# Microcontroller.net
KiCad netlist of a schematic drawn in Altium Designer
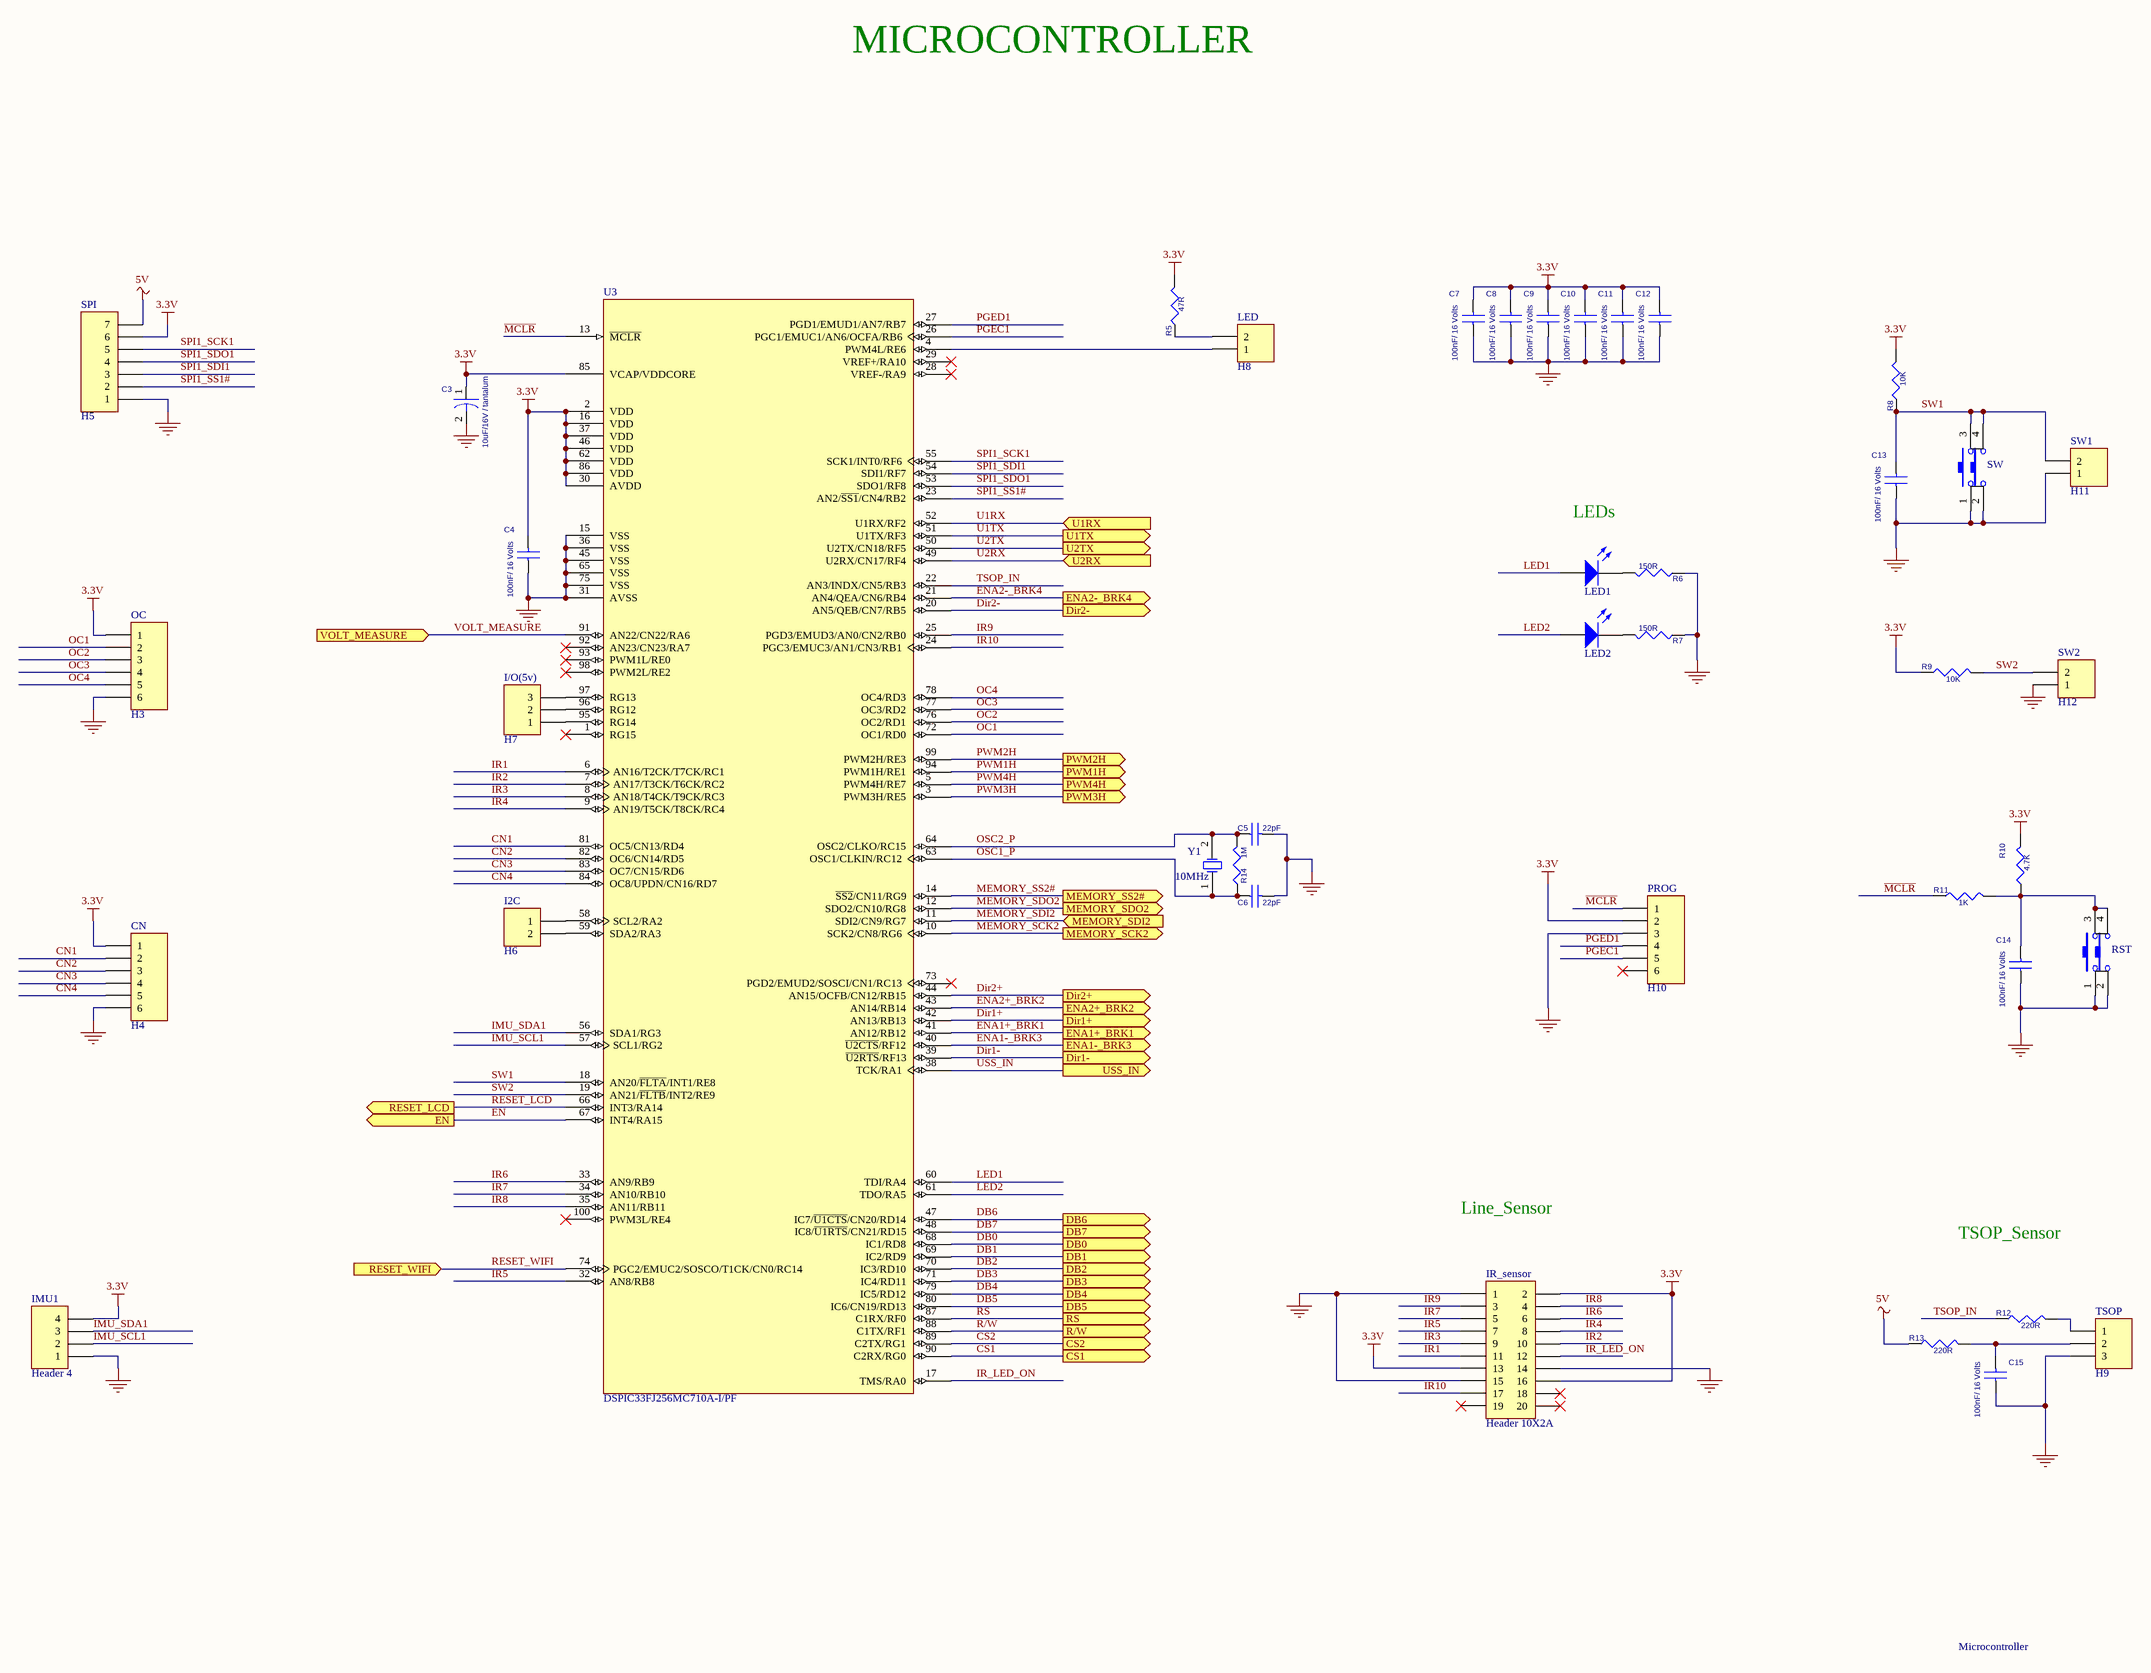
[diagram p0: Microcontroller.SchDoc]

(export (version "E")
  (design (tool "Eeschema 10.0.6"))
  (components
    (comp (ref "C3")
      (value "10uF/16V / tantalum")
      (footprint "CAP_TANTALUM")
      (libsource (lib "combined_cart_schematic_lib") (part "C_0"))
    )
    (comp (ref "C4")
      (value "100nF/ 16 Volts")
      (footprint "CAP_CERAMIC")
      (libsource (lib "combined_cart_schematic_lib") (part "CAP NP"))
    )
    (comp (ref "C5")
      (value "22pF")
      (footprint "CAP_CERAMIC")
      (libsource (lib "combined_cart_schematic_lib") (part "CAP NP"))
    )
    (comp (ref "C6")
      (value "22pF")
      (footprint "CAP_CERAMIC")
      (libsource (lib "combined_cart_schematic_lib") (part "CAP NP"))
    )
    (comp (ref "C7")
      (value "100nF/ 16 Volts")
      (footprint "CAP_CERAMIC")
      (libsource (lib "combined_cart_schematic_lib") (part "CAP NP"))
    )
    (comp (ref "C8")
      (value "100nF/ 16 Volts")
      (footprint "CAP_CERAMIC")
      (libsource (lib "combined_cart_schematic_lib") (part "CAP NP"))
    )
    (comp (ref "C9")
      (value "100nF/ 16 Volts")
      (footprint "CAP_CERAMIC")
      (libsource (lib "combined_cart_schematic_lib") (part "CAP NP"))
    )
    (comp (ref "C10")
      (value "100nF/ 16 Volts")
      (footprint "CAP_CERAMIC")
      (libsource (lib "combined_cart_schematic_lib") (part "CAP NP"))
    )
    (comp (ref "C11")
      (value "100nF/ 16 Volts")
      (footprint "CAP_CERAMIC")
      (libsource (lib "combined_cart_schematic_lib") (part "CAP NP"))
    )
    (comp (ref "C12")
      (value "100nF/ 16 Volts")
      (footprint "CAP_CERAMIC")
      (libsource (lib "combined_cart_schematic_lib") (part "CAP NP"))
    )
    (comp (ref "C13")
      (value "100nF/ 16 Volts")
      (footprint "CAP_CERAMIC")
      (libsource (lib "combined_cart_schematic_lib") (part "CAP NP"))
    )
    (comp (ref "C14")
      (value "100nF/ 16 Volts")
      (footprint "CAP_CERAMIC")
      (libsource (lib "combined_cart_schematic_lib") (part "CAP NP"))
    )
    (comp (ref "C15")
      (value "100nF/ 16 Volts")
      (footprint "CAP_CERAMIC")
      (libsource (lib "combined_cart_schematic_lib") (part "CAP NP"))
    )
    (comp (ref "CN")
      (value "H4")
      (footprint "1x6_single")
      (description "Header, 6-Pin")
      (fields (field (name "PUBLISHER") "Altium Limited"))
      (libsource (lib "combined_cart_schematic_lib") (part "Header 6"))
    )
    (comp (ref "I/O(5v)")
      (value "H7")
      (footprint "1x3_single - duplicate")
      (description "Header, 3-Pin")
      (fields (field (name "PUBLISHER") "Altium Limited"))
      (libsource (lib "combined_cart_schematic_lib") (part "Header 3"))
    )
    (comp (ref "I2C")
      (value "H6")
      (footprint "1x2_single")
      (description "Header, 2-Pin")
      (fields (field (name "PUBLISHER") "Altium Limited"))
      (libsource (lib "combined_cart_schematic_lib") (part "Header 2"))
    )
    (comp (ref "IMU1")
      (value "Header 4")
      (footprint "1x4_single")
      (description "Header, 4-Pin")
      (fields (field (name "PUBLISHER") "Altium Limited"))
      (libsource (lib "combined_cart_schematic_lib") (part "Header 4"))
    )
    (comp (ref "IR_sensor")
      (value "Header 10X2A")
      (footprint "10x2 row_ 2.54mm pitch")
      (description "Header, 20Pin, Dual row")
      (fields (field (name "PUBLISHER") "Altium Limited"))
      (libsource (lib "combined_cart_schematic_lib") (part "Header 10x2"))
    )
    (comp (ref "LED")
      (value "H8")
      (footprint "1x2_single")
      (description "Header, 2-Pin")
      (fields (field (name "PUBLISHER") "Altium Limited"))
      (libsource (lib "") (part "Header 2_1"))
    )
    (comp (ref "LED1")
      (value "LED1")
      (footprint "LED_SMD")
      (description "Typical INFRARED GaAs LED_throughole")
      (fields (field (name "PUBLISHER") "Altium Limited"))
      (libsource (lib "combined_cart_schematic_lib") (part "LED_SMD"))
    )
    (comp (ref "LED2")
      (value "LED2")
      (footprint "LED_SMD")
      (description "Typical INFRARED GaAs LED_throughole")
      (fields (field (name "PUBLISHER") "Altium Limited"))
      (libsource (lib "combined_cart_schematic_lib") (part "LED_SMD"))
    )
    (comp (ref "OC")
      (value "H3")
      (footprint "1x6_single")
      (description "Header, 6-Pin")
      (fields (field (name "PUBLISHER") "Altium Limited"))
      (libsource (lib "combined_cart_schematic_lib") (part "Header 6"))
    )
    (comp (ref "PROG")
      (value "H10")
      (footprint "1x6_single")
      (description "Header, 6-Pin")
      (fields (field (name "PUBLISHER") "Altium Limited"))
      (libsource (lib "combined_cart_schematic_lib") (part "Header 6"))
    )
    (comp (ref "R5")
      (value "47R")
      (footprint "RES_SMD")
      (libsource (lib "combined_cart_schematic_lib") (part "RESISTOR"))
    )
    (comp (ref "R6")
      (value "150R")
      (footprint "RES_SMD")
      (libsource (lib "combined_cart_schematic_lib") (part "RESISTOR"))
    )
    (comp (ref "R7")
      (value "150R")
      (footprint "RES_SMD")
      (libsource (lib "combined_cart_schematic_lib") (part "RESISTOR"))
    )
    (comp (ref "R8")
      (value "10K")
      (footprint "RES_SMD")
      (libsource (lib "combined_cart_schematic_lib") (part "RESISTOR"))
    )
    (comp (ref "R9")
      (value "10K")
      (footprint "RES_SMD")
      (libsource (lib "combined_cart_schematic_lib") (part "RESISTOR"))
    )
    (comp (ref "R10")
      (value "4.7K")
      (footprint "RES_SMD")
      (libsource (lib "combined_cart_schematic_lib") (part "RESISTOR"))
    )
    (comp (ref "R11")
      (value "1K")
      (footprint "RES_SMD")
      (libsource (lib "combined_cart_schematic_lib") (part "RESISTOR"))
    )
    (comp (ref "R12")
      (value "220R")
      (footprint "RES_SMD")
      (libsource (lib "combined_cart_schematic_lib") (part "RESISTOR"))
    )
    (comp (ref "R13")
      (value "220R")
      (footprint "RES_SMD")
      (libsource (lib "combined_cart_schematic_lib") (part "RESISTOR"))
    )
    (comp (ref "R14")
      (value "1M")
      (footprint "RES_SMD")
      (libsource (lib "combined_cart_schematic_lib") (part "RESISTOR"))
    )
    (comp (ref "RST")
      (value "SW-SMD")
      (footprint "SWITCH_SMD")
      (description "Switch")
      (fields (field (name "PUBLISHER") "Altium Limited"))
      (libsource (lib "combined_cart_schematic_lib") (part "SW-SMD"))
    )
    (comp (ref "SPI")
      (value "H5")
      (footprint "1x7_single")
      (description "Header, 6-Pin")
      (fields (field (name "PUBLISHER") "Altium Limited"))
      (libsource (lib "combined_cart_schematic_lib") (part "Header 7_1"))
    )
    (comp (ref "SW")
      (value "SW-SMD")
      (footprint "SWITCH_SMD")
      (description "Switch")
      (fields (field (name "PUBLISHER") "Altium Limited"))
      (libsource (lib "combined_cart_schematic_lib") (part "SW-SMD"))
    )
    (comp (ref "SW1")
      (value "H11")
      (footprint "1x2_single")
      (description "Header, 2-Pin")
      (fields (field (name "PUBLISHER") "Altium Limited"))
      (libsource (lib "") (part "Header 2_1"))
    )
    (comp (ref "SW2")
      (value "H12")
      (footprint "1x2_single")
      (description "Header, 2-Pin")
      (fields (field (name "PUBLISHER") "Altium Limited"))
      (libsource (lib "") (part "Header 2_1"))
    )
    (comp (ref "TSOP")
      (value "H9")
      (footprint "1x3_single - duplicate")
      (description "Header, 3-Pin")
      (fields (field (name "PUBLISHER") "Altium Limited"))
      (libsource (lib "") (part "Header 3_1"))
    )
    (comp (ref "U3")
      (value "DSPIC33FJ256MC710A-I/PF")
      (footprint "DSPIC33FJ256MC710-I/PF")
      (fields (field (name "PUBLISHER") "Altium Limited"))
      (libsource (lib "combined_cart_schematic_lib") (part "DSPIC33FJ256MC710-I/PF"))
    )
    (comp (ref "Y1")
      (value "10MHz")
      (footprint "CRYSTAL_10MHZ")
      (description "Crystal Oscillator")
      (fields (field (name "PUBLISHER") "Altium Limited"))
      (libsource (lib "combined_cart_schematic_lib") (part "XTAL"))
    )
  )
  (nets
    (net (code "1") (name "/CN1") (class "Default")
      (node (ref "CN") (pin "2") (pinfunction "2_2") (pintype "passive"))
      (node (ref "U3") (pin "81") (pinfunction "OC5/CN13/RD4_81") (pintype "bidirectional"))
    )
    (net (code "2") (name "/CN2") (class "Default")
      (node (ref "CN") (pin "3") (pinfunction "3_3") (pintype "passive"))
      (node (ref "U3") (pin "82") (pinfunction "OC6/CN14/RD5_82") (pintype "bidirectional"))
    )
    (net (code "3") (name "/CN3") (class "Default")
      (node (ref "CN") (pin "4") (pinfunction "4_4") (pintype "passive"))
      (node (ref "U3") (pin "83") (pinfunction "OC7/CN15/RD6_83") (pintype "bidirectional"))
    )
    (net (code "4") (name "/CN4") (class "Default")
      (node (ref "CN") (pin "5") (pinfunction "5_5") (pintype "passive"))
      (node (ref "U3") (pin "84") (pinfunction "OC8/UPDN/CN16/RD7_84") (pintype "bidirectional"))
    )
    (net (code "5") (name "/CS1") (class "Default")
      (node (ref "U3") (pin "90") (pinfunction "C2RX/RG0_90") (pintype "bidirectional"))
    )
    (net (code "6") (name "/CS2") (class "Default")
      (node (ref "U3") (pin "89") (pinfunction "C2TX/RG1_89") (pintype "bidirectional"))
    )
    (net (code "7") (name "/DB0") (class "Default")
      (node (ref "U3") (pin "68") (pinfunction "IC1/RD8_68") (pintype "bidirectional"))
    )
    (net (code "8") (name "/DB1") (class "Default")
      (node (ref "U3") (pin "69") (pinfunction "IC2/RD9_69") (pintype "bidirectional"))
    )
    (net (code "9") (name "/DB2") (class "Default")
      (node (ref "U3") (pin "70") (pinfunction "IC3/RD10_70") (pintype "bidirectional"))
    )
    (net (code "10") (name "/DB3") (class "Default")
      (node (ref "U3") (pin "71") (pinfunction "IC4/RD11_71") (pintype "bidirectional"))
    )
    (net (code "11") (name "/DB4") (class "Default")
      (node (ref "U3") (pin "79") (pinfunction "IC5/RD12_79") (pintype "bidirectional"))
    )
    (net (code "12") (name "/DB5") (class "Default")
      (node (ref "U3") (pin "80") (pinfunction "IC6/CN19/RD13_80") (pintype "bidirectional"))
    )
    (net (code "13") (name "/DB6") (class "Default")
      (node (ref "U3") (pin "47") (pinfunction "IC7/~{U1CTS}/CN20/RD14_47") (pintype "bidirectional"))
    )
    (net (code "14") (name "/DB7") (class "Default")
      (node (ref "U3") (pin "48") (pinfunction "IC8/~{U1RTS}/CN21/RD15_48") (pintype "bidirectional"))
    )
    (net (code "15") (name "/Dir1+") (class "Default")
      (node (ref "U3") (pin "42") (pinfunction "AN13/RB13_42") (pintype "bidirectional"))
    )
    (net (code "16") (name "/Dir1-") (class "Default")
      (node (ref "U3") (pin "39") (pinfunction "~{U2RTS}/RF13_39") (pintype "bidirectional"))
    )
    (net (code "17") (name "/Dir2+") (class "Default")
      (node (ref "U3") (pin "44") (pinfunction "AN15/OCFB/CN12/RB15_44") (pintype "bidirectional"))
    )
    (net (code "18") (name "/Dir2-") (class "Default")
      (node (ref "U3") (pin "20") (pinfunction "AN5/QEB/CN7/RB5_20") (pintype "bidirectional"))
    )
    (net (code "19") (name "/EN") (class "Default")
      (node (ref "U3") (pin "67") (pinfunction "INT4/RA15_67") (pintype "bidirectional"))
    )
    (net (code "20") (name "/ENA1+_BRK1") (class "Default")
      (node (ref "U3") (pin "41") (pinfunction "AN12/RB12_41") (pintype "bidirectional"))
    )
    (net (code "21") (name "/ENA1-_BRK3") (class "Default")
      (node (ref "U3") (pin "40") (pinfunction "~{U2CTS}/RF12_40") (pintype "bidirectional"))
    )
    (net (code "22") (name "/ENA2+_BRK2") (class "Default")
      (node (ref "U3") (pin "43") (pinfunction "AN14/RB14_43") (pintype "bidirectional"))
    )
    (net (code "23") (name "/ENA2-_BRK4") (class "Default")
      (node (ref "U3") (pin "21") (pinfunction "AN4/QEA/CN6/RB4_21") (pintype "bidirectional"))
    )
    (net (code "24") (name "/IMU_SCL1") (class "Default")
      (node (ref "IMU1") (pin "2") (pinfunction "2_2") (pintype "passive"))
      (node (ref "U3") (pin "57") (pinfunction "SCL1/RG2_57") (pintype "bidirectional"))
    )
    (net (code "25") (name "/IMU_SDA1") (class "Default")
      (node (ref "IMU1") (pin "3") (pinfunction "3_3") (pintype "passive"))
      (node (ref "U3") (pin "56") (pinfunction "SDA1/RG3_56") (pintype "bidirectional"))
    )
    (net (code "26") (name "/IR1") (class "Default")
      (node (ref "IR_sensor") (pin "11") (pinfunction "11_11") (pintype "passive"))
      (node (ref "U3") (pin "6") (pinfunction "AN16/T2CK/T7CK/RC1_6") (pintype "bidirectional"))
    )
    (net (code "27") (name "/IR2") (class "Default")
      (node (ref "IR_sensor") (pin "10") (pinfunction "10_10") (pintype "passive"))
      (node (ref "U3") (pin "7") (pinfunction "AN17/T3CK/T6CK/RC2_7") (pintype "bidirectional"))
    )
    (net (code "28") (name "/IR3") (class "Default")
      (node (ref "IR_sensor") (pin "9") (pinfunction "9_9") (pintype "passive"))
      (node (ref "U3") (pin "8") (pinfunction "AN18/T4CK/T9CK/RC3_8") (pintype "bidirectional"))
    )
    (net (code "29") (name "/IR4") (class "Default")
      (node (ref "IR_sensor") (pin "8") (pinfunction "8_8") (pintype "passive"))
      (node (ref "U3") (pin "9") (pinfunction "AN19/T5CK/T8CK/RC4_9") (pintype "bidirectional"))
    )
    (net (code "30") (name "/IR5") (class "Default")
      (node (ref "IR_sensor") (pin "7") (pinfunction "7_7") (pintype "passive"))
      (node (ref "U3") (pin "32") (pinfunction "AN8/RB8_32") (pintype "bidirectional"))
    )
    (net (code "31") (name "/IR6") (class "Default")
      (node (ref "IR_sensor") (pin "6") (pinfunction "6_6") (pintype "passive"))
      (node (ref "U3") (pin "33") (pinfunction "AN9/RB9_33") (pintype "bidirectional"))
    )
    (net (code "32") (name "/IR7") (class "Default")
      (node (ref "IR_sensor") (pin "5") (pinfunction "5_5") (pintype "passive"))
      (node (ref "U3") (pin "34") (pinfunction "AN10/RB10_34") (pintype "bidirectional"))
    )
    (net (code "33") (name "/IR8") (class "Default")
      (node (ref "IR_sensor") (pin "4") (pinfunction "4_4") (pintype "passive"))
      (node (ref "U3") (pin "35") (pinfunction "AN11/RB11_35") (pintype "bidirectional"))
    )
    (net (code "34") (name "/IR9") (class "Default")
      (node (ref "IR_sensor") (pin "3") (pinfunction "3_3") (pintype "passive"))
      (node (ref "U3") (pin "25") (pinfunction "PGD3/EMUD3/AN0/CN2/RB0_25") (pintype "bidirectional"))
    )
    (net (code "35") (name "/IR10") (class "Default")
      (node (ref "IR_sensor") (pin "17") (pinfunction "17_17") (pintype "passive"))
      (node (ref "U3") (pin "24") (pinfunction "PGC3/EMUC3/AN1/CN3/RB1_24") (pintype "bidirectional"))
    )
    (net (code "36") (name "/IR_LED_ON") (class "Default")
      (node (ref "IR_sensor") (pin "12") (pinfunction "12_12") (pintype "passive"))
      (node (ref "U3") (pin "17") (pinfunction "TMS/RA0_17") (pintype "bidirectional"))
    )
    (net (code "37") (name "/LED1") (class "Default")
      (node (ref "LED1") (pin "1") (pinfunction "A_1") (pintype "passive"))
      (node (ref "U3") (pin "60") (pinfunction "TDI/RA4_60") (pintype "bidirectional"))
    )
    (net (code "38") (name "/LED2") (class "Default")
      (node (ref "LED2") (pin "1") (pinfunction "A_1") (pintype "passive"))
      (node (ref "U3") (pin "61") (pinfunction "TDO/RA5_61") (pintype "bidirectional"))
    )
    (net (code "39") (name "/MEMORY_SCK2") (class "Default")
      (node (ref "U3") (pin "10") (pinfunction "SCK2/CN8/RG6_10") (pintype "bidirectional"))
    )
    (net (code "40") (name "/MEMORY_SDI2") (class "Default")
      (node (ref "U3") (pin "11") (pinfunction "SDI2/CN9/RG7_11") (pintype "bidirectional"))
    )
    (net (code "41") (name "/MEMORY_SDO2") (class "Default")
      (node (ref "U3") (pin "12") (pinfunction "SDO2/CN10/RG8_12") (pintype "bidirectional"))
    )
    (net (code "42") (name "/MEMORY_SS2#") (class "Default")
      (node (ref "U3") (pin "14") (pinfunction "~{SS2}/CN11/RG9_14") (pintype "bidirectional"))
    )
    (net (code "43") (name "/OC1") (class "Default")
      (node (ref "OC") (pin "2") (pinfunction "2_2") (pintype "passive"))
      (node (ref "U3") (pin "72") (pinfunction "OC1/RD0_72") (pintype "bidirectional"))
    )
    (net (code "44") (name "/OC2") (class "Default")
      (node (ref "OC") (pin "3") (pinfunction "3_3") (pintype "passive"))
      (node (ref "U3") (pin "76") (pinfunction "OC2/RD1_76") (pintype "bidirectional"))
    )
    (net (code "45") (name "/OC3") (class "Default")
      (node (ref "OC") (pin "4") (pinfunction "4_4") (pintype "passive"))
      (node (ref "U3") (pin "77") (pinfunction "OC3/RD2_77") (pintype "bidirectional"))
    )
    (net (code "46") (name "/OC4") (class "Default")
      (node (ref "OC") (pin "5") (pinfunction "5_5") (pintype "passive"))
      (node (ref "U3") (pin "78") (pinfunction "OC4/RD3_78") (pintype "bidirectional"))
    )
    (net (code "47") (name "/OSC1_P") (class "Default")
      (node (ref "C6") (pin "1") (pinfunction "1_1") (pintype "passive"))
      (node (ref "R14") (pin "1") (pinfunction "1_1") (pintype "passive"))
      (node (ref "U3") (pin "63") (pinfunction "OSC1/CLKIN/RC12_63") (pintype "bidirectional"))
      (node (ref "Y1") (pin "1") (pinfunction "OSC1_1") (pintype "passive"))
    )
    (net (code "48") (name "/OSC2_P") (class "Default")
      (node (ref "C5") (pin "1") (pinfunction "1_1") (pintype "passive"))
      (node (ref "R14") (pin "2") (pinfunction "2_2") (pintype "passive"))
      (node (ref "U3") (pin "64") (pinfunction "OSC2/CLKO/RC15_64") (pintype "bidirectional"))
      (node (ref "Y1") (pin "2") (pinfunction "OSC2_2") (pintype "passive"))
    )
    (net (code "49") (name "/PGEC1") (class "Default")
      (node (ref "PROG") (pin "5") (pinfunction "5_5") (pintype "passive"))
      (node (ref "U3") (pin "26") (pinfunction "PGC1/EMUC1/AN6/OCFA/RB6_26") (pintype "bidirectional"))
    )
    (net (code "50") (name "/PGED1") (class "Default")
      (node (ref "PROG") (pin "4") (pinfunction "4_4") (pintype "passive"))
      (node (ref "U3") (pin "27") (pinfunction "PGD1/EMUD1/AN7/RB7_27") (pintype "bidirectional"))
    )
    (net (code "51") (name "/PWM1H") (class "Default")
      (node (ref "U3") (pin "94") (pinfunction "PWM1H/RE1_94") (pintype "bidirectional"))
    )
    (net (code "52") (name "/PWM2H") (class "Default")
      (node (ref "U3") (pin "99") (pinfunction "PWM2H/RE3_99") (pintype "bidirectional"))
    )
    (net (code "53") (name "/PWM3H") (class "Default")
      (node (ref "U3") (pin "3") (pinfunction "PWM3H/RE5_3") (pintype "bidirectional"))
    )
    (net (code "54") (name "/PWM4H") (class "Default")
      (node (ref "U3") (pin "5") (pinfunction "PWM4H/RE7_5") (pintype "bidirectional"))
    )
    (net (code "55") (name "/RESET_LCD") (class "Default")
      (node (ref "U3") (pin "66") (pinfunction "INT3/RA14_66") (pintype "bidirectional"))
    )
    (net (code "56") (name "/RESET_WIFI") (class "Default")
      (node (ref "U3") (pin "74") (pinfunction "PGC2/EMUC2/SOSCO/T1CK/CN0/RC14_74") (pintype "bidirectional"))
    )
    (net (code "57") (name "/RS") (class "Default")
      (node (ref "U3") (pin "87") (pinfunction "C1RX/RF0_87") (pintype "bidirectional"))
    )
    (net (code "58") (name "/R{slash}W") (class "Default")
      (node (ref "U3") (pin "88") (pinfunction "C1TX/RF1_88") (pintype "bidirectional"))
    )
    (net (code "59") (name "/SPI1_SCK1") (class "Default")
      (node (ref "SPI") (pin "5") (pinfunction "5_5") (pintype "passive"))
      (node (ref "U3") (pin "55") (pinfunction "SCK1/INT0/RF6_55") (pintype "bidirectional"))
    )
    (net (code "60") (name "/SPI1_SDI1") (class "Default")
      (node (ref "SPI") (pin "3") (pinfunction "3_3") (pintype "passive"))
      (node (ref "U3") (pin "54") (pinfunction "SDI1/RF7_54") (pintype "bidirectional"))
    )
    (net (code "61") (name "/SPI1_SDO1") (class "Default")
      (node (ref "SPI") (pin "4") (pinfunction "4_4") (pintype "passive"))
      (node (ref "U3") (pin "53") (pinfunction "SDO1/RF8_53") (pintype "bidirectional"))
    )
    (net (code "62") (name "/SPI1_SS1#") (class "Default")
      (node (ref "SPI") (pin "2") (pinfunction "2_2") (pintype "passive"))
      (node (ref "U3") (pin "23") (pinfunction "AN2/~{SS1}/CN4/RB2_23") (pintype "bidirectional"))
    )
    (net (code "63") (name "/SW1") (class "Default")
      (node (ref "C13") (pin "2") (pinfunction "2_2") (pintype "passive"))
      (node (ref "R8") (pin "1") (pinfunction "1_1") (pintype "passive"))
      (node (ref "SW") (pin "3") (pintype "passive"))
      (node (ref "SW") (pin "4") (pintype "passive"))
      (node (ref "SW1") (pin "2") (pinfunction "2_2") (pintype "passive"))
      (node (ref "U3") (pin "18") (pinfunction "AN20/~{FLTA}/INT1/RE8_18") (pintype "bidirectional"))
    )
    (net (code "64") (name "/SW2") (class "Default")
      (node (ref "R9") (pin "2") (pinfunction "2_2") (pintype "passive"))
      (node (ref "SW2") (pin "2") (pinfunction "2_2") (pintype "passive"))
      (node (ref "U3") (pin "19") (pinfunction "AN21/~{FLTB}/INT2/RE9_19") (pintype "bidirectional"))
    )
    (net (code "65") (name "/TSOP_IN") (class "Default")
      (node (ref "R12") (pin "1") (pinfunction "1_1") (pintype "passive"))
      (node (ref "U3") (pin "22") (pinfunction "AN3/INDX/CN5/RB3_22") (pintype "bidirectional"))
    )
    (net (code "66") (name "/U1RX") (class "Default")
      (node (ref "U3") (pin "52") (pinfunction "U1RX/RF2_52") (pintype "bidirectional"))
    )
    (net (code "67") (name "/U1TX") (class "Default")
      (node (ref "U3") (pin "51") (pinfunction "U1TX/RF3_51") (pintype "bidirectional"))
    )
    (net (code "68") (name "/U2RX") (class "Default")
      (node (ref "U3") (pin "49") (pinfunction "U2RX/CN17/RF4_49") (pintype "bidirectional"))
    )
    (net (code "69") (name "/U2TX") (class "Default")
      (node (ref "U3") (pin "50") (pinfunction "U2TX/CN18/RF5_50") (pintype "bidirectional"))
    )
    (net (code "70") (name "/USS_IN") (class "Default")
      (node (ref "U3") (pin "38") (pinfunction "TCK/RA1_38") (pintype "bidirectional"))
    )
    (net (code "71") (name "/VOLT_MEASURE") (class "Default")
      (node (ref "U3") (pin "91") (pinfunction "AN22/CN22/RA6_91") (pintype "bidirectional"))
    )
    (net (code "72") (name "/~{MCLR}") (class "Default")
      (node (ref "PROG") (pin "1") (pinfunction "1_1") (pintype "passive"))
      (node (ref "R11") (pin "1") (pinfunction "1_1") (pintype "passive"))
      (node (ref "U3") (pin "13") (pinfunction "~{MCLR}_13") (pintype "input"))
    )
    (net (code "73") (name "3.3V") (class "Default")
      (node (ref "C10") (pin "2") (pinfunction "2_2") (pintype "passive"))
      (node (ref "C11") (pin "2") (pinfunction "2_2") (pintype "passive"))
      (node (ref "C12") (pin "2") (pinfunction "2_2") (pintype "passive"))
      (node (ref "C3") (pin "1") (pinfunction "1_1") (pintype "passive"))
      (node (ref "C4") (pin "2") (pinfunction "2_2") (pintype "passive"))
      (node (ref "C7") (pin "2") (pinfunction "2_2") (pintype "passive"))
      (node (ref "C8") (pin "2") (pinfunction "2_2") (pintype "passive"))
      (node (ref "C9") (pin "2") (pinfunction "2_2") (pintype "passive"))
      (node (ref "CN") (pin "1") (pinfunction "1_1") (pintype "passive"))
      (node (ref "IMU1") (pin "4") (pinfunction "4_4") (pintype "passive"))
      (node (ref "IR_sensor") (pin "13") (pinfunction "13_13") (pintype "passive"))
      (node (ref "IR_sensor") (pin "16") (pinfunction "16_16") (pintype "passive"))
      (node (ref "IR_sensor") (pin "2") (pinfunction "2_2") (pintype "passive"))
      (node (ref "OC") (pin "1") (pinfunction "1_1") (pintype "passive"))
      (node (ref "PROG") (pin "2") (pinfunction "2_2") (pintype "passive"))
      (node (ref "R10") (pin "2") (pinfunction "2_2") (pintype "passive"))
      (node (ref "R5") (pin "2") (pinfunction "2_2") (pintype "passive"))
      (node (ref "R8") (pin "2") (pinfunction "2_2") (pintype "passive"))
      (node (ref "R9") (pin "1") (pinfunction "1_1") (pintype "passive"))
      (node (ref "SPI") (pin "6") (pinfunction "6_6") (pintype "passive"))
      (node (ref "U3") (pin "16") (pinfunction "VDD_16") (pintype "power_in"))
      (node (ref "U3") (pin "2") (pinfunction "VDD_2") (pintype "power_in"))
      (node (ref "U3") (pin "30") (pinfunction "AVDD_30") (pintype "power_in"))
      (node (ref "U3") (pin "37") (pinfunction "VDD_37") (pintype "power_in"))
      (node (ref "U3") (pin "46") (pinfunction "VDD_46") (pintype "power_in"))
      (node (ref "U3") (pin "62") (pinfunction "VDD_62") (pintype "power_in"))
      (node (ref "U3") (pin "85") (pinfunction "VCAP/VDDCORE_85") (pintype "power_in"))
      (node (ref "U3") (pin "86") (pinfunction "VDD_86") (pintype "power_in"))
    )
    (net (code "74") (name "5V") (class "Default")
      (node (ref "R13") (pin "1") (pinfunction "1_1") (pintype "passive"))
      (node (ref "SPI") (pin "7") (pinfunction "7_7") (pintype "passive"))
    )
    (net (code "75") (name "GND_POWER") (class "Default")
      (node (ref "C10") (pin "1") (pinfunction "1_1") (pintype "passive"))
      (node (ref "C11") (pin "1") (pinfunction "1_1") (pintype "passive"))
      (node (ref "C12") (pin "1") (pinfunction "1_1") (pintype "passive"))
      (node (ref "C13") (pin "1") (pinfunction "1_1") (pintype "passive"))
      (node (ref "C14") (pin "1") (pinfunction "1_1") (pintype "passive"))
      (node (ref "C15") (pin "1") (pinfunction "1_1") (pintype "passive"))
      (node (ref "C3") (pin "2") (pinfunction "2_2") (pintype "passive"))
      (node (ref "C4") (pin "1") (pinfunction "1_1") (pintype "passive"))
      (node (ref "C5") (pin "2") (pinfunction "2_2") (pintype "passive"))
      (node (ref "C6") (pin "2") (pinfunction "2_2") (pintype "passive"))
      (node (ref "C7") (pin "1") (pinfunction "1_1") (pintype "passive"))
      (node (ref "C8") (pin "1") (pinfunction "1_1") (pintype "passive"))
      (node (ref "C9") (pin "1") (pinfunction "1_1") (pintype "passive"))
      (node (ref "CN") (pin "6") (pinfunction "6_6") (pintype "passive"))
      (node (ref "IMU1") (pin "1") (pinfunction "1_1") (pintype "passive"))
      (node (ref "IR_sensor") (pin "1") (pinfunction "1_1") (pintype "passive"))
      (node (ref "IR_sensor") (pin "14") (pinfunction "14_14") (pintype "passive"))
      (node (ref "IR_sensor") (pin "15") (pinfunction "15_15") (pintype "passive"))
      (node (ref "OC") (pin "6") (pinfunction "6_6") (pintype "passive"))
      (node (ref "PROG") (pin "3") (pinfunction "3_3") (pintype "passive"))
      (node (ref "R6") (pin "1") (pinfunction "1_1") (pintype "passive"))
      (node (ref "R7") (pin "1") (pinfunction "1_1") (pintype "passive"))
      (node (ref "RST") (pin "1") (pintype "passive"))
      (node (ref "RST") (pin "2") (pintype "passive"))
      (node (ref "SPI") (pin "1") (pinfunction "1_1") (pintype "passive"))
      (node (ref "SW") (pin "1") (pintype "passive"))
      (node (ref "SW") (pin "2") (pintype "passive"))
      (node (ref "SW1") (pin "1") (pinfunction "1_1") (pintype "passive"))
      (node (ref "SW2") (pin "1") (pinfunction "1_1") (pintype "passive"))
      (node (ref "TSOP") (pin "3") (pinfunction "3_3") (pintype "passive"))
      (node (ref "U3") (pin "15") (pinfunction "VSS_15") (pintype "power_in"))
      (node (ref "U3") (pin "31") (pinfunction "AVSS_31") (pintype "power_in"))
      (node (ref "U3") (pin "36") (pinfunction "VSS_36") (pintype "power_in"))
      (node (ref "U3") (pin "45") (pinfunction "VSS_45") (pintype "power_in"))
      (node (ref "U3") (pin "65") (pinfunction "VSS_65") (pintype "power_in"))
      (node (ref "U3") (pin "75") (pinfunction "VSS_75") (pintype "power_in"))
    )
    (net (code "76") (name "Net-(C14-Pad2)") (class "Default")
      (node (ref "C14") (pin "2") (pinfunction "2_2") (pintype "passive"))
      (node (ref "R10") (pin "1") (pinfunction "1_1") (pintype "passive"))
      (node (ref "R11") (pin "2") (pinfunction "2_2") (pintype "passive"))
      (node (ref "RST") (pin "3") (pintype "passive"))
      (node (ref "RST") (pin "4") (pintype "passive"))
    )
    (net (code "77") (name "Net-(C15-Pad2)") (class "Default")
      (node (ref "C15") (pin "2") (pinfunction "2_2") (pintype "passive"))
      (node (ref "R13") (pin "2") (pinfunction "2_2") (pintype "passive"))
      (node (ref "TSOP") (pin "2") (pinfunction "2_2") (pintype "passive"))
    )
    (net (code "78") (name "Net-(LED-Pad2)") (class "Default")
      (node (ref "LED") (pin "2") (pinfunction "2_2") (pintype "passive"))
      (node (ref "R5") (pin "1") (pinfunction "1_1") (pintype "passive"))
    )
    (net (code "79") (name "Net-(LED1-K)") (class "Default")
      (node (ref "LED1") (pin "2") (pinfunction "K_2") (pintype "passive"))
      (node (ref "R6") (pin "2") (pinfunction "2_2") (pintype "passive"))
    )
    (net (code "80") (name "Net-(LED2-K)") (class "Default")
      (node (ref "LED2") (pin "2") (pinfunction "K_2") (pintype "passive"))
      (node (ref "R7") (pin "2") (pinfunction "2_2") (pintype "passive"))
    )
    (net (code "81") (name "Net-(R12-Pad2)") (class "Default")
      (node (ref "R12") (pin "2") (pinfunction "2_2") (pintype "passive"))
      (node (ref "TSOP") (pin "1") (pinfunction "1_1") (pintype "passive"))
    )
    (net (code "82") (name "Net-(U3-PWM4L{slash}RE6)") (class "Default")
      (node (ref "LED") (pin "1") (pinfunction "1_1") (pintype "passive"))
      (node (ref "U3") (pin "4") (pinfunction "PWM4L/RE6_4") (pintype "bidirectional"))
    )
    (net (code "83") (name "Net-(U3-RG12)") (class "Default")
      (node (ref "I/O(5v)") (pin "2") (pinfunction "2_2") (pintype "passive"))
      (node (ref "U3") (pin "96") (pinfunction "RG12_96") (pintype "bidirectional"))
    )
    (net (code "84") (name "Net-(U3-RG13)") (class "Default")
      (node (ref "I/O(5v)") (pin "3") (pinfunction "3_3") (pintype "passive"))
      (node (ref "U3") (pin "97") (pinfunction "RG13_97") (pintype "bidirectional"))
    )
    (net (code "85") (name "Net-(U3-RG14)") (class "Default")
      (node (ref "I/O(5v)") (pin "1") (pinfunction "1_1") (pintype "passive"))
      (node (ref "U3") (pin "95") (pinfunction "RG14_95") (pintype "bidirectional"))
    )
    (net (code "86") (name "Net-(U3-SCL2{slash}RA2)") (class "Default")
      (node (ref "I2C") (pin "1") (pinfunction "1_1") (pintype "passive"))
      (node (ref "U3") (pin "58") (pinfunction "SCL2/RA2_58") (pintype "bidirectional"))
    )
    (net (code "87") (name "Net-(U3-SDA2{slash}RA3)") (class "Default")
      (node (ref "I2C") (pin "2") (pinfunction "2_2") (pintype "passive"))
      (node (ref "U3") (pin "59") (pinfunction "SDA2/RA3_59") (pintype "bidirectional"))
    )
    (net (code "88") (name "unconnected-(IR_sensor-Pad18)") (class "Default")
      (node (ref "IR_sensor") (pin "18") (pinfunction "18_18") (pintype "passive+no_connect"))
    )
    (net (code "89") (name "unconnected-(IR_sensor-Pad19)") (class "Default")
      (node (ref "IR_sensor") (pin "19") (pinfunction "19_19") (pintype "passive+no_connect"))
    )
    (net (code "90") (name "unconnected-(IR_sensor-Pad20)") (class "Default")
      (node (ref "IR_sensor") (pin "20") (pinfunction "20_20") (pintype "passive+no_connect"))
    )
    (net (code "91") (name "unconnected-(PROG-Pad6)") (class "Default")
      (node (ref "PROG") (pin "6") (pinfunction "6_6") (pintype "passive+no_connect"))
    )
    (net (code "92") (name "unconnected-(U3-AN23{slash}CN23{slash}RA7-Pad92)") (class "Default")
      (node (ref "U3") (pin "92") (pinfunction "AN23/CN23/RA7_92") (pintype "bidirectional+no_connect"))
    )
    (net (code "93") (name "unconnected-(U3-PGD2{slash}EMUD2{slash}SOSCI{slash}CN1{slash}RC13-Pad73)") (class "Default")
      (node (ref "U3") (pin "73") (pinfunction "PGD2/EMUD2/SOSCI/CN1/RC13_73") (pintype "bidirectional+no_connect"))
    )
    (net (code "94") (name "unconnected-(U3-PWM1L{slash}RE0-Pad93)") (class "Default")
      (node (ref "U3") (pin "93") (pinfunction "PWM1L/RE0_93") (pintype "bidirectional+no_connect"))
    )
    (net (code "95") (name "unconnected-(U3-PWM2L{slash}RE2-Pad98)") (class "Default")
      (node (ref "U3") (pin "98") (pinfunction "PWM2L/RE2_98") (pintype "bidirectional+no_connect"))
    )
    (net (code "96") (name "unconnected-(U3-PWM3L{slash}RE4-Pad100)") (class "Default")
      (node (ref "U3") (pin "100") (pinfunction "PWM3L/RE4_100") (pintype "bidirectional+no_connect"))
    )
    (net (code "97") (name "unconnected-(U3-RG15-Pad1)") (class "Default")
      (node (ref "U3") (pin "1") (pinfunction "RG15_1") (pintype "bidirectional+no_connect"))
    )
    (net (code "98") (name "unconnected-(U3-VREF+{slash}RA10-Pad29)") (class "Default")
      (node (ref "U3") (pin "29") (pinfunction "VREF+/RA10_29") (pintype "bidirectional+no_connect"))
    )
    (net (code "99") (name "unconnected-(U3-VREF-{slash}RA9-Pad28)") (class "Default")
      (node (ref "U3") (pin "28") (pinfunction "VREF-/RA9_28") (pintype "bidirectional+no_connect"))
    )
  )
)
